# BuckBoost.net
KiCad netlist of a schematic drawn in Altium Designer
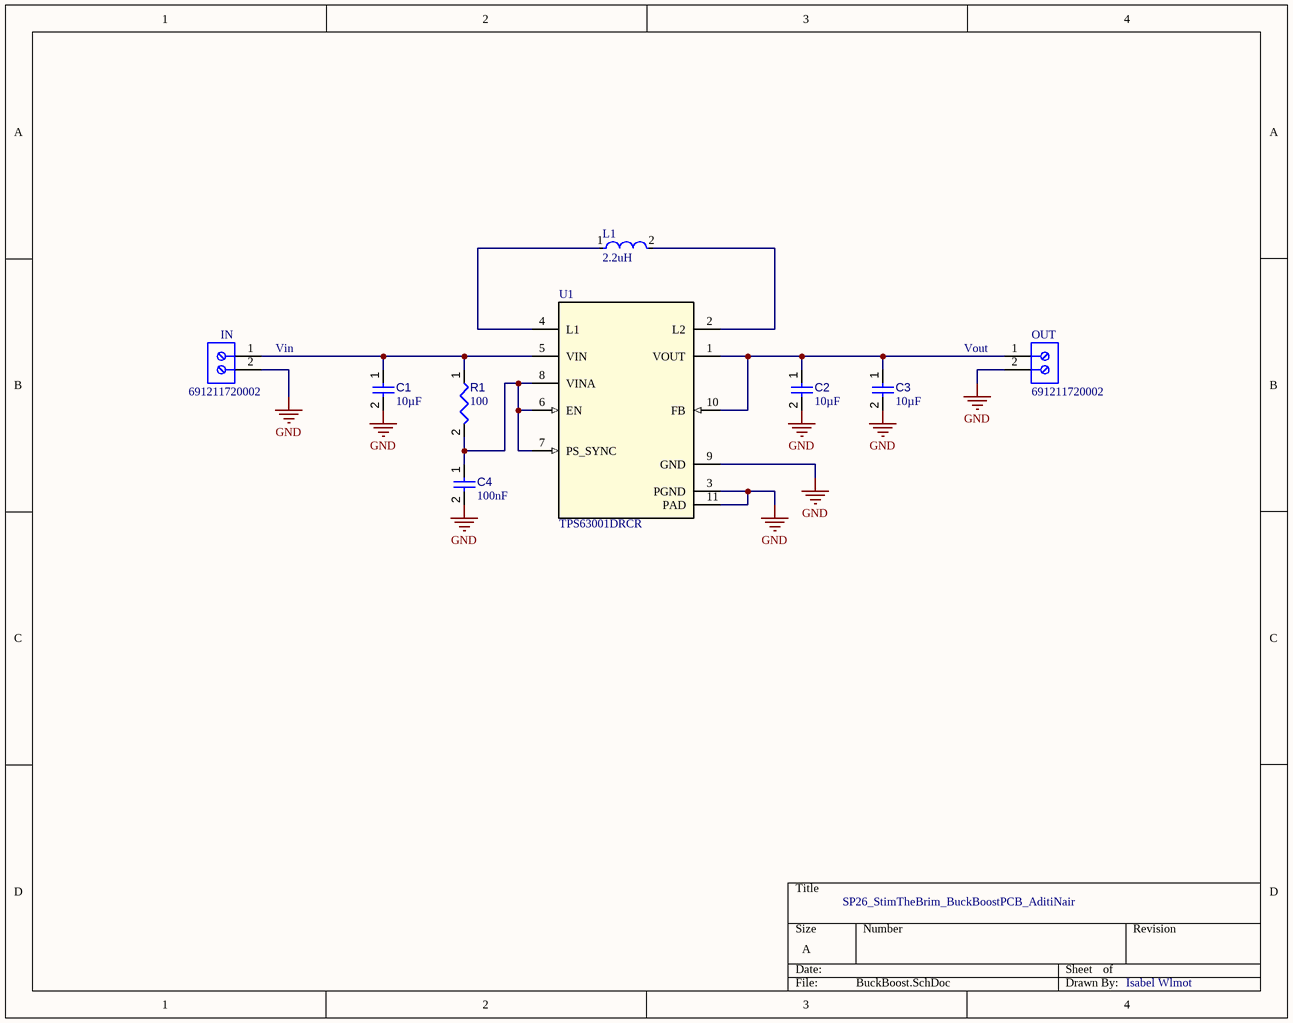
[diagram p0: BuckBoost.SchDoc]

(export (version "E")
  (design (tool "Eeschema 10.0.6"))
  (components
    (comp (ref "C1")
      (value "10µF")
      (footprint "CAPC0805(2012)145_L")
      (description "Chip Capacitor, 10µF +/-20%, 25V, 0805, Thickness 1.45 mm")
      (fields (field (name "TOLERANCE") "10%") (field (name "Comment") "Capacitor 10µF +/-20% 25V 0805"))
      (libsource (lib "Aditi Nair") (part "CAP-NP-2"))
    )
    (comp (ref "C2")
      (value "10µF")
      (footprint "CAPC0805(2012)145_L")
      (description "Chip Capacitor, 10µF +/-20%, 25V, 0805, Thickness 1.45 mm")
      (fields (field (name "TOLERANCE") "10%") (field (name "Comment") "Capacitor 10µF +/-20% 25V 0805"))
      (libsource (lib "Aditi Nair") (part "CAP-NP-2"))
    )
    (comp (ref "C3")
      (value "10µF")
      (footprint "CAPC0805(2012)145_L")
      (description "Chip Capacitor, 10µF +/-20%, 25V, 0805, Thickness 1.45 mm")
      (fields (field (name "TOLERANCE") "10%") (field (name "Comment") "Capacitor 10µF +/-20% 25V 0805"))
      (libsource (lib "Aditi Nair") (part "CAP-NP-2"))
    )
    (comp (ref "C4")
      (value "100nF")
      (footprint "CAPC2013X95X50LL10T25")
      (description "Chip Capacitor, 100 nF, +/- 10%, 50 V, 0805 (2012 Metric)")
      (fields (field (name "TOLERANCE") "10%") (field (name "Comment") "Capacitor 100 nF +/-10% 50 V 0805"))
      (libsource (lib "Aditi Nair") (part "CAP-NP-2"))
    )
    (comp (ref "IN")
      (value "691211720002")
      (footprint "691211720002")
      (description "211 Series 5MM Pitch Straight, Pcb Terminal Block, Through Hole, 2 Way")
      (fields (field (name "VOLTAGE") "300V"))
      (libsource (lib "Altium Content Vault") (part "TBL - 1R - 02P - Screw"))
    )
    (comp (ref "L1")
      (value "2.2uH")
      (footprint "FP-82103C-MFG")
      (description "FIXED IND 10UH 500MA 400MOHM SMD")
      (fields (field (name "TOLERANCE") "10%"))
      (libsource (lib "Altium Content Vault") (part "725321dda6339637d4d059423bc1c3c"))
    )
    (comp (ref "OUT")
      (value "691211720002")
      (footprint "691211720002")
      (description "211 Series 5MM Pitch Straight, Pcb Terminal Block, Through Hole, 2 Way")
      (fields (field (name "VOLTAGE") "300V"))
      (libsource (lib "Altium Content Vault") (part "TBL - 1R - 02P - Screw"))
    )
    (comp (ref "R1")
      (value "100")
      (footprint "RESC0402(1005)_L")
      (description "Chip Resistor, 100 Ohms, +/-1 %, 63 mW, -55 to 155 degC, 0402")
      (fields (field (name "POWER") "63mW") (field (name "TOLERANCE") "1%"))
      (libsource (lib "Aditi Nair") (part "RES-2"))
    )
    (comp (ref "U1")
      (value "TPS63001DRCR")
      (footprint "DRC0010J")
      (fields
        (field (name "ALTERNATE_PARTNUMBER") "TPS63001DRCT")
        (field (name "MANUFACTURER") "Texas Instruments")
        (field (name "COPYRIGHT") "Copyright (C) 2025 Ultra Librarian. All rights reserved.")
      )
      (libsource (lib "TPS63001DRCR") (part "TPS63001DRCR"))
    )
  )
  (nets
    (net (code "1") (name "GND") (class "Default")
      (node (ref "C1") (pin "2") (pinfunction "2_2") (pintype "passive"))
      (node (ref "C2") (pin "2") (pinfunction "2_2") (pintype "passive"))
      (node (ref "C3") (pin "2") (pinfunction "2_2") (pintype "passive"))
      (node (ref "C4") (pin "2") (pinfunction "2_2") (pintype "passive"))
      (node (ref "IN") (pin "2") (pinfunction "2_2") (pintype "passive"))
      (node (ref "OUT") (pin "2") (pinfunction "2_2") (pintype "passive"))
      (node (ref "U1") (pin "11") (pinfunction "PAD_11") (pintype "power_in"))
      (node (ref "U1") (pin "3") (pinfunction "PGND_3") (pintype "power_in"))
      (node (ref "U1") (pin "9") (pinfunction "GND_9") (pintype "power_in"))
    )
    (net (code "2") (name "Net-(U1-EN)") (class "Default")
      (node (ref "C4") (pin "1") (pinfunction "1_1") (pintype "passive"))
      (node (ref "R1") (pin "2") (pinfunction "2_2") (pintype "passive"))
      (node (ref "U1") (pin "6") (pinfunction "EN_6") (pintype "input"))
      (node (ref "U1") (pin "7") (pinfunction "PS_SYNC_7") (pintype "input"))
      (node (ref "U1") (pin "8") (pinfunction "VINA_8") (pintype "power_in"))
    )
    (net (code "3") (name "Net-(U1-FB)") (class "Default")
      (node (ref "C2") (pin "1") (pinfunction "1_1") (pintype "passive"))
      (node (ref "C3") (pin "1") (pinfunction "1_1") (pintype "passive"))
      (node (ref "OUT") (pin "1") (pinfunction "1_1") (pintype "passive"))
      (node (ref "U1") (pin "1") (pinfunction "VOUT_1") (pintype "power_in"))
      (node (ref "U1") (pin "10") (pinfunction "FB_10") (pintype "input"))
    )
    (net (code "4") (name "Net-(U1-L1)") (class "Default")
      (node (ref "L1") (pin "1") (pinfunction "1_1") (pintype "passive"))
      (node (ref "U1") (pin "4") (pinfunction "L1_4") (pintype "passive"))
    )
    (net (code "5") (name "Net-(U1-L2)") (class "Default")
      (node (ref "L1") (pin "2") (pinfunction "2_2") (pintype "passive"))
      (node (ref "U1") (pin "2") (pinfunction "L2_2") (pintype "passive"))
    )
    (net (code "6") (name "Net-(U1-VIN)") (class "Default")
      (node (ref "C1") (pin "1") (pinfunction "1_1") (pintype "passive"))
      (node (ref "IN") (pin "1") (pinfunction "1_1") (pintype "passive"))
      (node (ref "R1") (pin "1") (pinfunction "1_1") (pintype "passive"))
      (node (ref "U1") (pin "5") (pinfunction "VIN_5") (pintype "power_in"))
    )
  )
)
